# rec.net
KiCad netlist of a schematic drawn in EAGLE
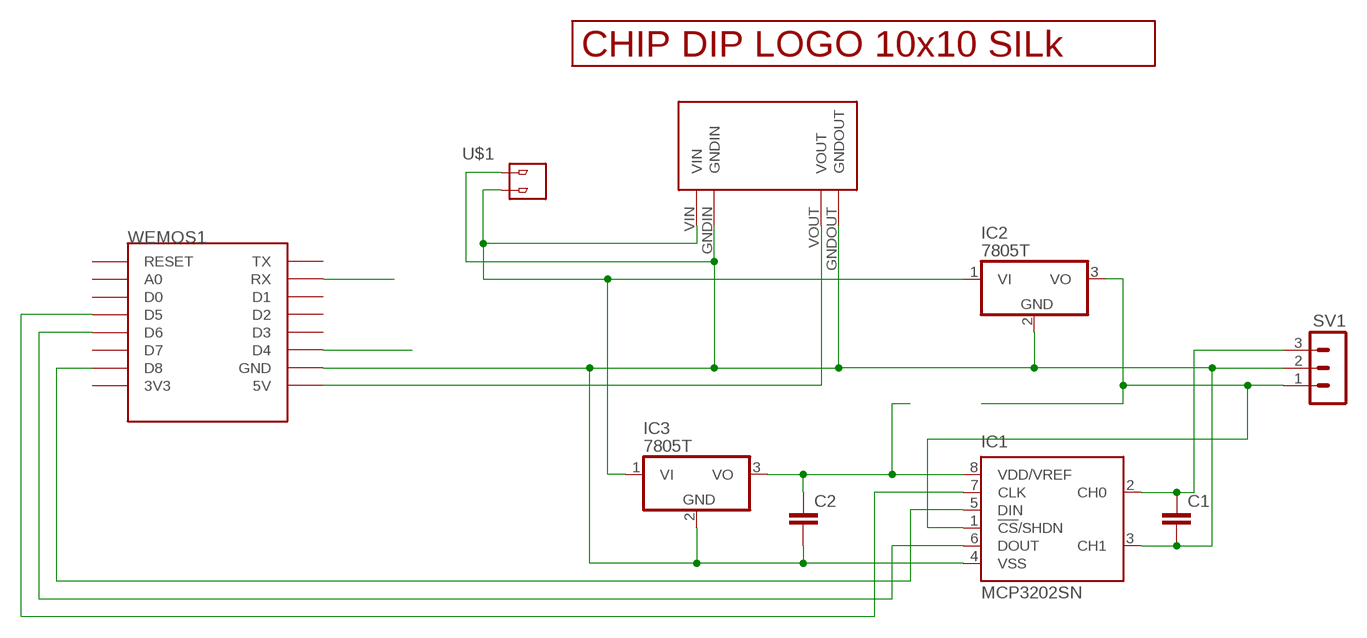
[diagram p0: schematic, sheet 1]

(export (version "E")
  (design (tool "Eeschema 10.0.6"))
  (components
    (comp (ref "C1")
      (value "C-EUC0805")
      (footprint "eagle-import:C0805")
      (libsource (lib "eagle-import") (part "C-EUC0805"))
    )
    (comp (ref "C2")
      (value "C-EUC0805")
      (footprint "eagle-import:C0805")
      (libsource (lib "eagle-import") (part "C-EUC0805"))
    )
    (comp (ref "IC1")
      (value "MCP3202SN")
      (footprint "eagle-import:SO-08")
      (fields (field (name "MF") "MICROCHIP") (field (name "MPN") "MCP3202-CI/SN"))
      (libsource (lib "eagle-import") (part "MCP3202SN"))
    )
    (comp (ref "IC2")
      (value "7805T")
      (footprint "eagle-import:TO220H")
      (libsource (lib "eagle-import") (part "78T05"))
    )
    (comp (ref "IC3")
      (value "7805T")
      (footprint "eagle-import:TO220H")
      (libsource (lib "eagle-import") (part "78T05"))
    )
    (comp (ref "SV1")
      (value "MA03-1")
      (footprint "eagle-import:MA03-1")
      (libsource (lib "eagle-import") (part "MA03-1"))
    )
    (comp (ref "U$1")
      (value "2_PIN_CONNECTOR")
      (footprint "eagle-import:2_SCREW_PIN")
      (libsource (lib "eagle-import") (part "2_PIN_CONNECTOR"))
    )
    (comp (ref "U$2")
      (value "LOGO_10X10_SILK")
      (footprint "eagle-import:LOGO2_10X10_SILK")
      (libsource (lib "eagle-import") (part "LOGO_10X10_SILK"))
    )
    (comp (ref "U$3")
      (value "MP1584EN")
      (footprint "eagle-import:MP1584EN")
      (libsource (lib "eagle-import") (part "MP1584EN"))
    )
    (comp (ref "WEMOS1")
      (value "WEMOS-D1-MINI")
      (footprint "eagle-import:WEMOS-D1-MINI")
      (libsource (lib "eagle-import") (part "WEMOS-D1-MINI"))
    )
  )
  (nets
    (net (code "1") (name "Net-(IC1-CH0)") (class "Default")
      (node (ref "C1") (pin "1") (pinfunction "1_1") (pintype "passive"))
      (node (ref "IC1") (pin "2") (pinfunction "CH0_2") (pintype "input"))
      (node (ref "SV1") (pin "3") (pinfunction "3_3") (pintype "passive"))
    )
    (net (code "2") (name "Net-(IC1-CH1)") (class "Default")
      (node (ref "C1") (pin "2") (pinfunction "2_2") (pintype "passive"))
      (node (ref "C2") (pin "2") (pinfunction "2_2") (pintype "passive"))
      (node (ref "IC1") (pin "3") (pinfunction "CH1_3") (pintype "input"))
      (node (ref "IC1") (pin "4") (pinfunction "VSS_4") (pintype "input"))
      (node (ref "IC2") (pin "2") (pinfunction "GND_2") (pintype "passive"))
      (node (ref "IC3") (pin "2") (pinfunction "GND_2") (pintype "passive"))
      (node (ref "SV1") (pin "2") (pinfunction "2_2") (pintype "passive"))
      (node (ref "U$1") (pin "P$1") (pinfunction "1_P$1") (pintype "passive"))
      (node (ref "U$3") (pin "GNDIN") (pinfunction "GNDIN_GNDIN") (pintype "power_in"))
      (node (ref "U$3") (pin "GNDOUT") (pinfunction "GNDOUT_GNDOUT") (pintype "power_in"))
      (node (ref "WEMOS1") (pin "GND") (pinfunction "GND_GND") (pintype "bidirectional"))
    )
    (net (code "3") (name "Net-(IC1-CLK)") (class "Default")
      (node (ref "IC1") (pin "7") (pinfunction "CLK_7") (pintype "input"))
      (node (ref "WEMOS1") (pin "D5") (pinfunction "D5_D5") (pintype "bidirectional"))
    )
    (net (code "4") (name "Net-(IC1-DIN)") (class "Default")
      (node (ref "IC1") (pin "5") (pinfunction "DIN_5") (pintype "input"))
      (node (ref "WEMOS1") (pin "D8") (pinfunction "D8_D8") (pintype "bidirectional"))
    )
    (net (code "5") (name "Net-(IC1-DOUT)") (class "Default")
      (node (ref "IC1") (pin "6") (pinfunction "DOUT_6") (pintype "input"))
      (node (ref "WEMOS1") (pin "D6") (pinfunction "D6_D6") (pintype "bidirectional"))
    )
    (net (code "6") (name "Net-(IC1-VDD{slash}VREF)") (class "Default")
      (node (ref "C2") (pin "1") (pinfunction "1_1") (pintype "passive"))
      (node (ref "IC1") (pin "8") (pinfunction "VDD/VREF_8") (pintype "input"))
      (node (ref "IC3") (pin "3") (pinfunction "VO_3") (pintype "passive"))
    )
    (net (code "7") (name "Net-(IC1-~{CS}{slash}SHDN)") (class "Default")
      (node (ref "IC1") (pin "1") (pinfunction "~{CS}/SHDN_1") (pintype "input"))
      (node (ref "IC2") (pin "3") (pinfunction "VO_3") (pintype "passive"))
      (node (ref "SV1") (pin "1") (pinfunction "1_1") (pintype "passive"))
    )
    (net (code "8") (name "Net-(IC2-VI)") (class "Default")
      (node (ref "IC2") (pin "1") (pinfunction "VI_1") (pintype "input"))
      (node (ref "IC3") (pin "1") (pinfunction "VI_1") (pintype "input"))
      (node (ref "U$1") (pin "P$2") (pinfunction "2_P$2") (pintype "passive"))
      (node (ref "U$3") (pin "VIN") (pinfunction "VIN_VIN") (pintype "power_in"))
    )
    (net (code "9") (name "Net-(U$3-PadVOUT)") (class "Default")
      (node (ref "U$3") (pin "VOUT") (pinfunction "VOUT_VOUT") (pintype "power_in"))
      (node (ref "WEMOS1") (pin "5V") (pinfunction "5V_5V") (pintype "bidirectional"))
    )
    (net (code "10") (name "unconnected-(WEMOS1-Pad3V3)") (class "Default")
      (node (ref "WEMOS1") (pin "3V3") (pinfunction "3V3_3V3") (pintype "bidirectional"))
    )
    (net (code "11") (name "unconnected-(WEMOS1-PadA0)") (class "Default")
      (node (ref "WEMOS1") (pin "A0") (pinfunction "A0_A0") (pintype "bidirectional"))
    )
    (net (code "12") (name "unconnected-(WEMOS1-PadD0)") (class "Default")
      (node (ref "WEMOS1") (pin "D0") (pinfunction "D0_D0") (pintype "bidirectional"))
    )
    (net (code "13") (name "unconnected-(WEMOS1-PadD1)") (class "Default")
      (node (ref "WEMOS1") (pin "D1") (pinfunction "D1_D1") (pintype "bidirectional"))
    )
    (net (code "14") (name "unconnected-(WEMOS1-PadD2)") (class "Default")
      (node (ref "WEMOS1") (pin "D2") (pinfunction "D2_D2") (pintype "bidirectional"))
    )
    (net (code "15") (name "unconnected-(WEMOS1-PadD3)") (class "Default")
      (node (ref "WEMOS1") (pin "D3") (pinfunction "D3_D3") (pintype "bidirectional"))
    )
    (net (code "16") (name "unconnected-(WEMOS1-PadD4)") (class "Default")
      (node (ref "WEMOS1") (pin "D4") (pinfunction "D4_D4") (pintype "bidirectional"))
    )
    (net (code "17") (name "unconnected-(WEMOS1-PadD7)") (class "Default")
      (node (ref "WEMOS1") (pin "D7") (pinfunction "D7_D7") (pintype "bidirectional"))
    )
    (net (code "18") (name "unconnected-(WEMOS1-PadRESET)") (class "Default")
      (node (ref "WEMOS1") (pin "RESET") (pinfunction "RESET_RESET") (pintype "bidirectional"))
    )
    (net (code "19") (name "unconnected-(WEMOS1-PadRX)") (class "Default")
      (node (ref "WEMOS1") (pin "RX") (pinfunction "RX_RX") (pintype "bidirectional"))
    )
    (net (code "20") (name "unconnected-(WEMOS1-PadTX)") (class "Default")
      (node (ref "WEMOS1") (pin "TX") (pinfunction "TX_TX") (pintype "bidirectional"))
    )
  )
)
